# Cherry_Mx_ByZ.net
KiCad netlist of a schematic drawn in Altium Designer
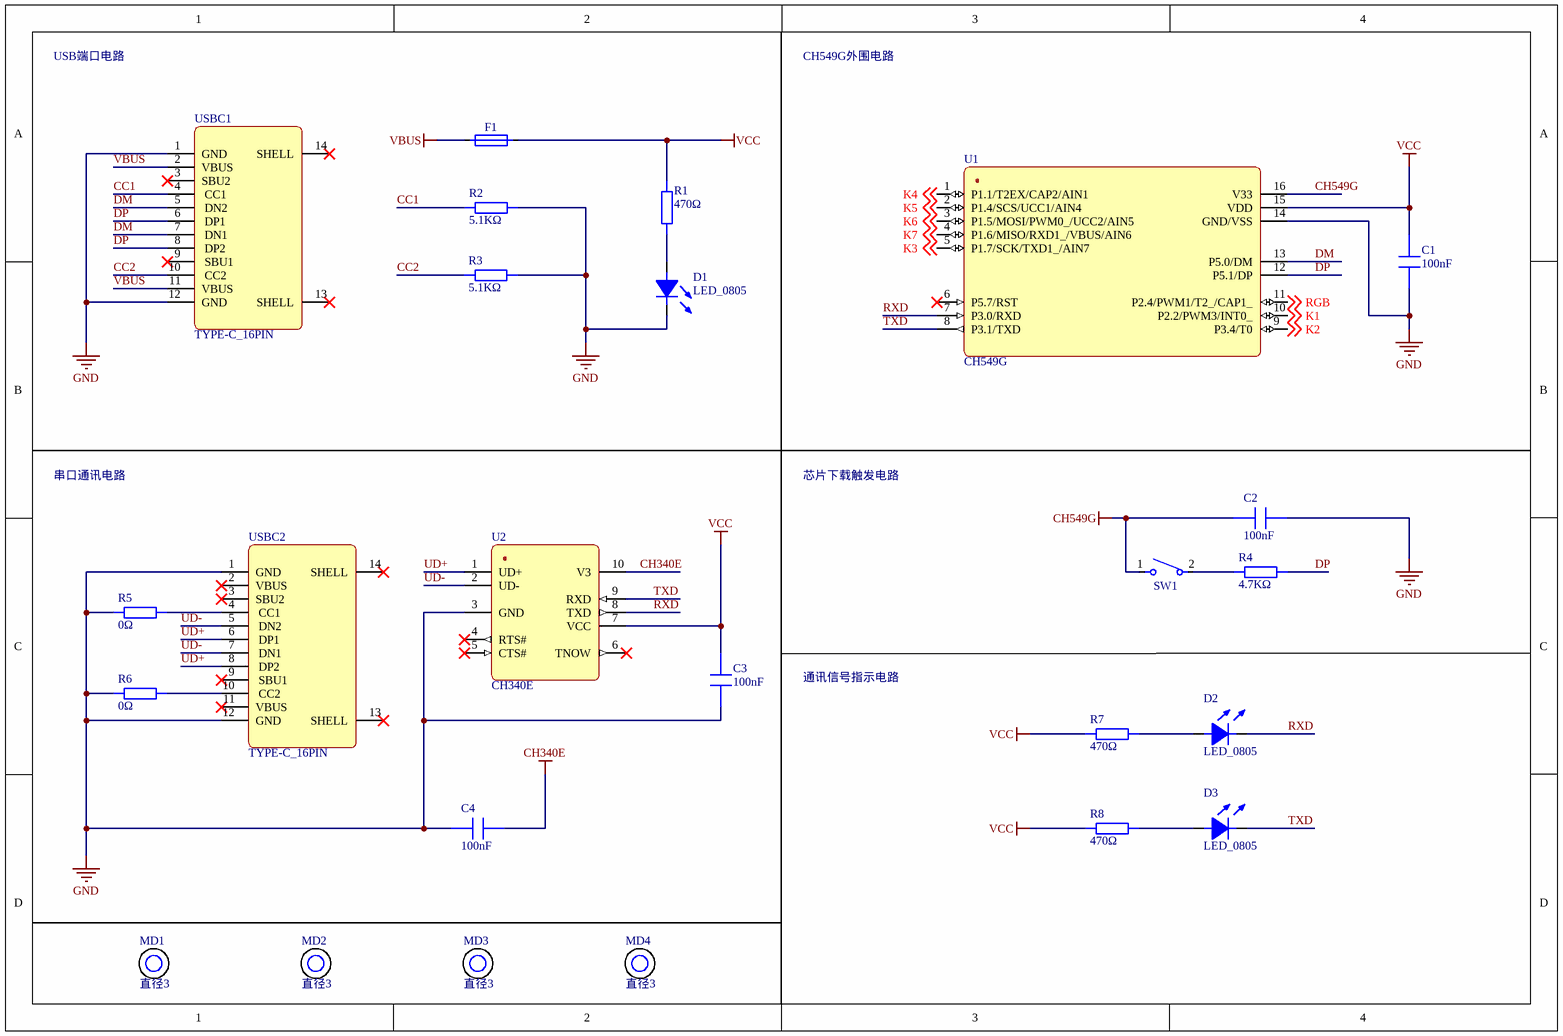
[diagram p0: Cherry_Mx_ByZ.SchDoc]

(export (version "E")
  (design (tool "Eeschema 10.0.6"))
  (components
    (comp (ref "C1")
      (value "100nF")
      (footprint "SM_C_0805")
      (description "贴片电容")
      (libsource (lib "Lib_Personal_ByZ") (part "C0805"))
    )
    (comp (ref "C2")
      (value "100nF")
      (footprint "SM_C_0805")
      (description "贴片电容")
      (libsource (lib "Lib_Personal_ByZ") (part "C0805"))
    )
    (comp (ref "C3")
      (value "100nF")
      (footprint "SM_C_0805")
      (description "贴片电容")
      (libsource (lib "Lib_Personal_ByZ") (part "C0805"))
    )
    (comp (ref "C4")
      (value "100nF")
      (footprint "SM_C_0805")
      (description "贴片电容")
      (libsource (lib "Lib_Personal_ByZ") (part "C0805"))
    )
    (comp (ref "D1")
      (value "LED_0805")
      (footprint "LED_0805_White")
      (description "发光二极管")
      (libsource (lib "Lib_Personal_ByZ") (part "LED_0805"))
    )
    (comp (ref "D2")
      (value "LED_0805")
      (footprint "LED_0805_White")
      (description "发光二极管")
      (libsource (lib "Lib_Personal_ByZ") (part "LED_0805"))
    )
    (comp (ref "D3")
      (value "LED_0805")
      (footprint "LED_0805_White")
      (description "发光二极管")
      (libsource (lib "Lib_Personal_ByZ") (part "LED_0805"))
    )
    (comp (ref "F1")
      (value "F_0805")
      (footprint "SMD_F_0805")
      (description "自恢复保险丝")
      (libsource (lib "Lib_Personal_ByZ") (part "F_0805"))
    )
    (comp (ref "MD1")
      (value "直径3")
      (footprint "M3")
      (description "直径3mm过孔")
      (fields (field (name "Comment") "M3"))
      (libsource (lib "Lib_Personal_ByZ") (part "M3"))
    )
    (comp (ref "MD2")
      (value "直径3")
      (footprint "M3")
      (description "直径3mm过孔")
      (fields (field (name "Comment") "M3"))
      (libsource (lib "Lib_Personal_ByZ") (part "M3"))
    )
    (comp (ref "MD3")
      (value "直径3")
      (footprint "M3")
      (description "直径3mm过孔")
      (fields (field (name "Comment") "M3"))
      (libsource (lib "Lib_Personal_ByZ") (part "M3"))
    )
    (comp (ref "MD4")
      (value "直径3")
      (footprint "M3")
      (description "直径3mm过孔")
      (fields (field (name "Comment") "M3"))
      (libsource (lib "Lib_Personal_ByZ") (part "M3"))
    )
    (comp (ref "R1")
      (value "470Ω")
      (footprint "SM_R_0805")
      (description "贴片电阻")
      (libsource (lib "Lib_Personal_ByZ") (part "R0805"))
    )
    (comp (ref "R2")
      (value "5.1KΩ")
      (footprint "SM_R_0805")
      (description "贴片电阻")
      (libsource (lib "Lib_Personal_ByZ") (part "R0805"))
    )
    (comp (ref "R3")
      (value "5.1KΩ")
      (footprint "SM_R_0805")
      (description "贴片电阻")
      (libsource (lib "Lib_Personal_ByZ") (part "R0805"))
    )
    (comp (ref "R4")
      (value "4.7KΩ")
      (footprint "SM_R_0805")
      (description "贴片电阻")
      (libsource (lib "Lib_Personal_ByZ") (part "R0805"))
    )
    (comp (ref "R5")
      (value "0Ω")
      (footprint "SM_R_0805")
      (description "贴片电阻")
      (libsource (lib "Lib_Personal_ByZ") (part "R0805"))
    )
    (comp (ref "R6")
      (value "0Ω")
      (footprint "SM_R_0805")
      (description "贴片电阻")
      (libsource (lib "Lib_Personal_ByZ") (part "R0805"))
    )
    (comp (ref "R7")
      (value "470Ω")
      (footprint "SM_R_0805")
      (description "贴片电阻")
      (libsource (lib "Lib_Personal_ByZ") (part "R0805"))
    )
    (comp (ref "R8")
      (value "470Ω")
      (footprint "SM_R_0805")
      (description "贴片电阻")
      (libsource (lib "Lib_Personal_ByZ") (part "R0805"))
    )
    (comp (ref "SW1")
      (value "轻触开关")
      (footprint "SW_L6W3.5")
      (description "按钮轻触开关")
      (libsource (lib "Lib_Personal_ByZ") (part "轻触开关"))
    )
    (comp (ref "U1")
      (value "CH549G")
      (footprint "SOP-16")
      (description "沁恒USB芯片")
      (libsource (lib "Lib_Personal_ByZ") (part "CH549G"))
    )
    (comp (ref "U2")
      (value "CH340E")
      (footprint "MSOP-10")
      (description "沁恒串口转TTL")
      (libsource (lib "Lib_Personal_ByZ") (part "CH340E"))
    )
    (comp (ref "USBC1")
      (value "TYPE-C_16PIN")
      (footprint "SMD_TYPE-C_16PIN_WS")
      (description "USB连接器")
      (libsource (lib "Lib_Personal_ByZ") (part "TYPE-C_16PIN"))
    )
    (comp (ref "USBC2")
      (value "TYPE-C_16PIN")
      (footprint "SMD_TYPE-C_16PIN_WS")
      (description "USB连接器")
      (libsource (lib "Lib_Personal_ByZ") (part "TYPE-C_16PIN"))
    )
  )
  (nets
    (net (code "1") (name "/CC1") (class "Default")
      (node (ref "R2") (pin "1") (pinfunction "1_1") (pintype "passive"))
      (node (ref "USBC1") (pin "4") (pinfunction "_CC1_4") (pintype "passive"))
    )
    (net (code "2") (name "/CC2") (class "Default")
      (node (ref "R3") (pin "1") (pinfunction "1_1") (pintype "passive"))
      (node (ref "USBC1") (pin "10") (pinfunction "_CC2_10") (pintype "passive"))
    )
    (net (code "3") (name "/DM") (class "Default")
      (node (ref "U1") (pin "13") (pinfunction "P5.0/DM_13") (pintype "passive"))
      (node (ref "USBC1") (pin "5") (pinfunction "_DN2_5") (pintype "passive"))
      (node (ref "USBC1") (pin "7") (pinfunction "_DN1_7") (pintype "passive"))
    )
    (net (code "4") (name "/DP") (class "Default")
      (node (ref "R4") (pin "2") (pinfunction "2_2") (pintype "passive"))
      (node (ref "U1") (pin "12") (pinfunction "P5.1/DP_12") (pintype "passive"))
      (node (ref "USBC1") (pin "6") (pinfunction "_DP1_6") (pintype "passive"))
      (node (ref "USBC1") (pin "8") (pinfunction "_DP2_8") (pintype "passive"))
    )
    (net (code "5") (name "/RXD") (class "Default")
      (node (ref "D2") (pin "2") (pinfunction "2_2") (pintype "passive"))
      (node (ref "U1") (pin "7") (pinfunction "P3.0/RXD_7") (pintype "input"))
      (node (ref "U2") (pin "8") (pinfunction "TXD_8") (pintype "output"))
    )
    (net (code "6") (name "/TXD") (class "Default")
      (node (ref "D3") (pin "2") (pinfunction "2_2") (pintype "passive"))
      (node (ref "U1") (pin "8") (pinfunction "P3.1/TXD_8") (pintype "output"))
      (node (ref "U2") (pin "9") (pinfunction "RXD_9") (pintype "input"))
    )
    (net (code "7") (name "/UD+") (class "Default")
      (node (ref "U2") (pin "1") (pinfunction "UD+_1") (pintype "passive"))
      (node (ref "USBC2") (pin "6") (pinfunction "_DP1_6") (pintype "passive"))
      (node (ref "USBC2") (pin "8") (pinfunction "_DP2_8") (pintype "passive"))
    )
    (net (code "8") (name "/UD-") (class "Default")
      (node (ref "U2") (pin "2") (pinfunction "UD-_2") (pintype "passive"))
      (node (ref "USBC2") (pin "5") (pinfunction "_DN2_5") (pintype "passive"))
      (node (ref "USBC2") (pin "7") (pinfunction "_DN1_7") (pintype "passive"))
    )
    (net (code "9") (name "CH340E") (class "Default")
      (node (ref "C4") (pin "1") (pinfunction "1_1") (pintype "passive"))
      (node (ref "U2") (pin "10") (pinfunction "V3_10") (pintype "power_in"))
    )
    (net (code "10") (name "CH549G") (class "Default")
      (node (ref "C2") (pin "2") (pinfunction "2_2") (pintype "passive"))
      (node (ref "SW1") (pin "1") (pinfunction "1_1") (pintype "passive"))
      (node (ref "U1") (pin "16") (pinfunction "V33_16") (pintype "power_in"))
    )
    (net (code "11") (name "GND") (class "Default")
      (node (ref "C1") (pin "1") (pinfunction "1_1") (pintype "passive"))
      (node (ref "C2") (pin "1") (pinfunction "1_1") (pintype "passive"))
      (node (ref "C3") (pin "1") (pinfunction "1_1") (pintype "passive"))
      (node (ref "C4") (pin "2") (pinfunction "2_2") (pintype "passive"))
      (node (ref "D1") (pin "2") (pinfunction "2_2") (pintype "passive"))
      (node (ref "R2") (pin "2") (pinfunction "2_2") (pintype "passive"))
      (node (ref "R3") (pin "2") (pinfunction "2_2") (pintype "passive"))
      (node (ref "R5") (pin "1") (pinfunction "1_1") (pintype "passive"))
      (node (ref "R6") (pin "1") (pinfunction "1_1") (pintype "passive"))
      (node (ref "U1") (pin "14") (pinfunction "GND/VSS_14") (pintype "power_in"))
      (node (ref "U2") (pin "3") (pinfunction "GND_3") (pintype "power_in"))
      (node (ref "USBC1") (pin "1") (pinfunction "GND_1") (pintype "passive"))
      (node (ref "USBC1") (pin "12") (pinfunction "GND_12") (pintype "passive"))
      (node (ref "USBC2") (pin "1") (pinfunction "GND_1") (pintype "passive"))
      (node (ref "USBC2") (pin "12") (pinfunction "GND_12") (pintype "passive"))
    )
    (net (code "12") (name "K1") (class "Default")
      (node (ref "U1") (pin "10") (pinfunction "P2.2/PWM3/INT0__10") (pintype "bidirectional"))
    )
    (net (code "13") (name "K2") (class "Default")
      (node (ref "U1") (pin "9") (pinfunction "P3.4/T0_9") (pintype "bidirectional"))
    )
    (net (code "14") (name "K3") (class "Default")
      (node (ref "U1") (pin "5") (pinfunction "P1.7/SCK/TXD1_/AIN7_5") (pintype "bidirectional"))
    )
    (net (code "15") (name "K4") (class "Default")
      (node (ref "U1") (pin "1") (pinfunction "P1.1/T2EX/CAP2/AIN1_1") (pintype "bidirectional"))
    )
    (net (code "16") (name "K5") (class "Default")
      (node (ref "U1") (pin "2") (pinfunction "P1.4/SCS/UCC1/AIN4_2") (pintype "bidirectional"))
    )
    (net (code "17") (name "K6") (class "Default")
      (node (ref "U1") (pin "3") (pinfunction "P1.5/MOSI/PWM0_/UCC2/AIN5_3") (pintype "bidirectional"))
    )
    (net (code "18") (name "K7") (class "Default")
      (node (ref "U1") (pin "4") (pinfunction "P1.6/MISO/RXD1_/VBUS/AIN6_4") (pintype "bidirectional"))
    )
    (net (code "19") (name "Net-(D1-Pad1)") (class "Default")
      (node (ref "D1") (pin "1") (pinfunction "1_1") (pintype "passive"))
      (node (ref "R1") (pin "2") (pinfunction "2_2") (pintype "passive"))
    )
    (net (code "20") (name "Net-(D2-Pad1)") (class "Default")
      (node (ref "D2") (pin "1") (pinfunction "1_1") (pintype "passive"))
      (node (ref "R7") (pin "2") (pinfunction "2_2") (pintype "passive"))
    )
    (net (code "21") (name "Net-(D3-Pad1)") (class "Default")
      (node (ref "D3") (pin "1") (pinfunction "1_1") (pintype "passive"))
      (node (ref "R8") (pin "2") (pinfunction "2_2") (pintype "passive"))
    )
    (net (code "22") (name "Net-(R4-Pad1)") (class "Default")
      (node (ref "R4") (pin "1") (pinfunction "1_1") (pintype "passive"))
      (node (ref "SW1") (pin "2") (pinfunction "2_2") (pintype "passive"))
    )
    (net (code "23") (name "Net-(USBC2-_CC1)") (class "Default")
      (node (ref "R5") (pin "2") (pinfunction "2_2") (pintype "passive"))
      (node (ref "USBC2") (pin "4") (pinfunction "_CC1_4") (pintype "passive"))
    )
    (net (code "24") (name "Net-(USBC2-_CC2)") (class "Default")
      (node (ref "R6") (pin "2") (pinfunction "2_2") (pintype "passive"))
      (node (ref "USBC2") (pin "10") (pinfunction "_CC2_10") (pintype "passive"))
    )
    (net (code "25") (name "RGB") (class "Default")
      (node (ref "U1") (pin "11") (pinfunction "P2.4/PWM1/T2_/CAP1__11") (pintype "bidirectional"))
    )
    (net (code "26") (name "VBUS") (class "Default")
      (node (ref "F1") (pin "1") (pinfunction "1_1") (pintype "passive"))
      (node (ref "USBC1") (pin "11") (pinfunction "VBUS_11") (pintype "passive"))
      (node (ref "USBC1") (pin "2") (pinfunction "VBUS_2") (pintype "passive"))
    )
    (net (code "27") (name "VCC") (class "Default")
      (node (ref "C1") (pin "2") (pinfunction "2_2") (pintype "passive"))
      (node (ref "C3") (pin "2") (pinfunction "2_2") (pintype "passive"))
      (node (ref "F1") (pin "2") (pinfunction "2_2") (pintype "passive"))
      (node (ref "R1") (pin "1") (pinfunction "1_1") (pintype "passive"))
      (node (ref "R7") (pin "1") (pinfunction "1_1") (pintype "passive"))
      (node (ref "R8") (pin "1") (pinfunction "1_1") (pintype "passive"))
      (node (ref "U1") (pin "15") (pinfunction "VDD_15") (pintype "power_in"))
      (node (ref "U2") (pin "7") (pinfunction "VCC_7") (pintype "power_in"))
    )
    (net (code "28") (name "unconnected-(U1-P5.7{slash}RST-Pad6)") (class "Default")
      (node (ref "U1") (pin "6") (pinfunction "P5.7/RST_6") (pintype "input+no_connect"))
    )
    (net (code "29") (name "unconnected-(U2-CTS#-Pad5)") (class "Default")
      (node (ref "U2") (pin "5") (pinfunction "CTS#_5") (pintype "input+no_connect"))
    )
    (net (code "30") (name "unconnected-(U2-RTS#-Pad4)") (class "Default")
      (node (ref "U2") (pin "4") (pinfunction "RTS#_4") (pintype "output+no_connect"))
    )
    (net (code "31") (name "unconnected-(U2-TNOW-Pad6)") (class "Default")
      (node (ref "U2") (pin "6") (pinfunction "TNOW_6") (pintype "output+no_connect"))
    )
    (net (code "32") (name "unconnected-(USBC1-SBU2-Pad3)") (class "Default")
      (node (ref "USBC1") (pin "3") (pinfunction "SBU2_3") (pintype "passive+no_connect"))
    )
    (net (code "33") (name "unconnected-(USBC1-SHELL-Pad13)") (class "Default")
      (node (ref "USBC1") (pin "13") (pinfunction "SHELL_13") (pintype "passive+no_connect"))
    )
    (net (code "34") (name "unconnected-(USBC1-SHELL-Pad14)") (class "Default")
      (node (ref "USBC1") (pin "14") (pinfunction "SHELL_14") (pintype "passive+no_connect"))
    )
    (net (code "35") (name "unconnected-(USBC1-_SBU1-Pad9)") (class "Default")
      (node (ref "USBC1") (pin "9") (pinfunction "_SBU1_9") (pintype "passive+no_connect"))
    )
    (net (code "36") (name "unconnected-(USBC2-SBU2-Pad3)") (class "Default")
      (node (ref "USBC2") (pin "3") (pinfunction "SBU2_3") (pintype "passive+no_connect"))
    )
    (net (code "37") (name "unconnected-(USBC2-SHELL-Pad13)") (class "Default")
      (node (ref "USBC2") (pin "13") (pinfunction "SHELL_13") (pintype "passive+no_connect"))
    )
    (net (code "38") (name "unconnected-(USBC2-SHELL-Pad14)") (class "Default")
      (node (ref "USBC2") (pin "14") (pinfunction "SHELL_14") (pintype "passive+no_connect"))
    )
    (net (code "39") (name "unconnected-(USBC2-VBUS-Pad2)") (class "Default")
      (node (ref "USBC2") (pin "2") (pinfunction "VBUS_2") (pintype "passive+no_connect"))
    )
    (net (code "40") (name "unconnected-(USBC2-VBUS-Pad11)") (class "Default")
      (node (ref "USBC2") (pin "11") (pinfunction "VBUS_11") (pintype "passive+no_connect"))
    )
    (net (code "41") (name "unconnected-(USBC2-_SBU1-Pad9)") (class "Default")
      (node (ref "USBC2") (pin "9") (pinfunction "_SBU1_9") (pintype "passive+no_connect"))
    )
  )
)
